# USB.net
KiCad netlist of a schematic drawn in Altium Designer
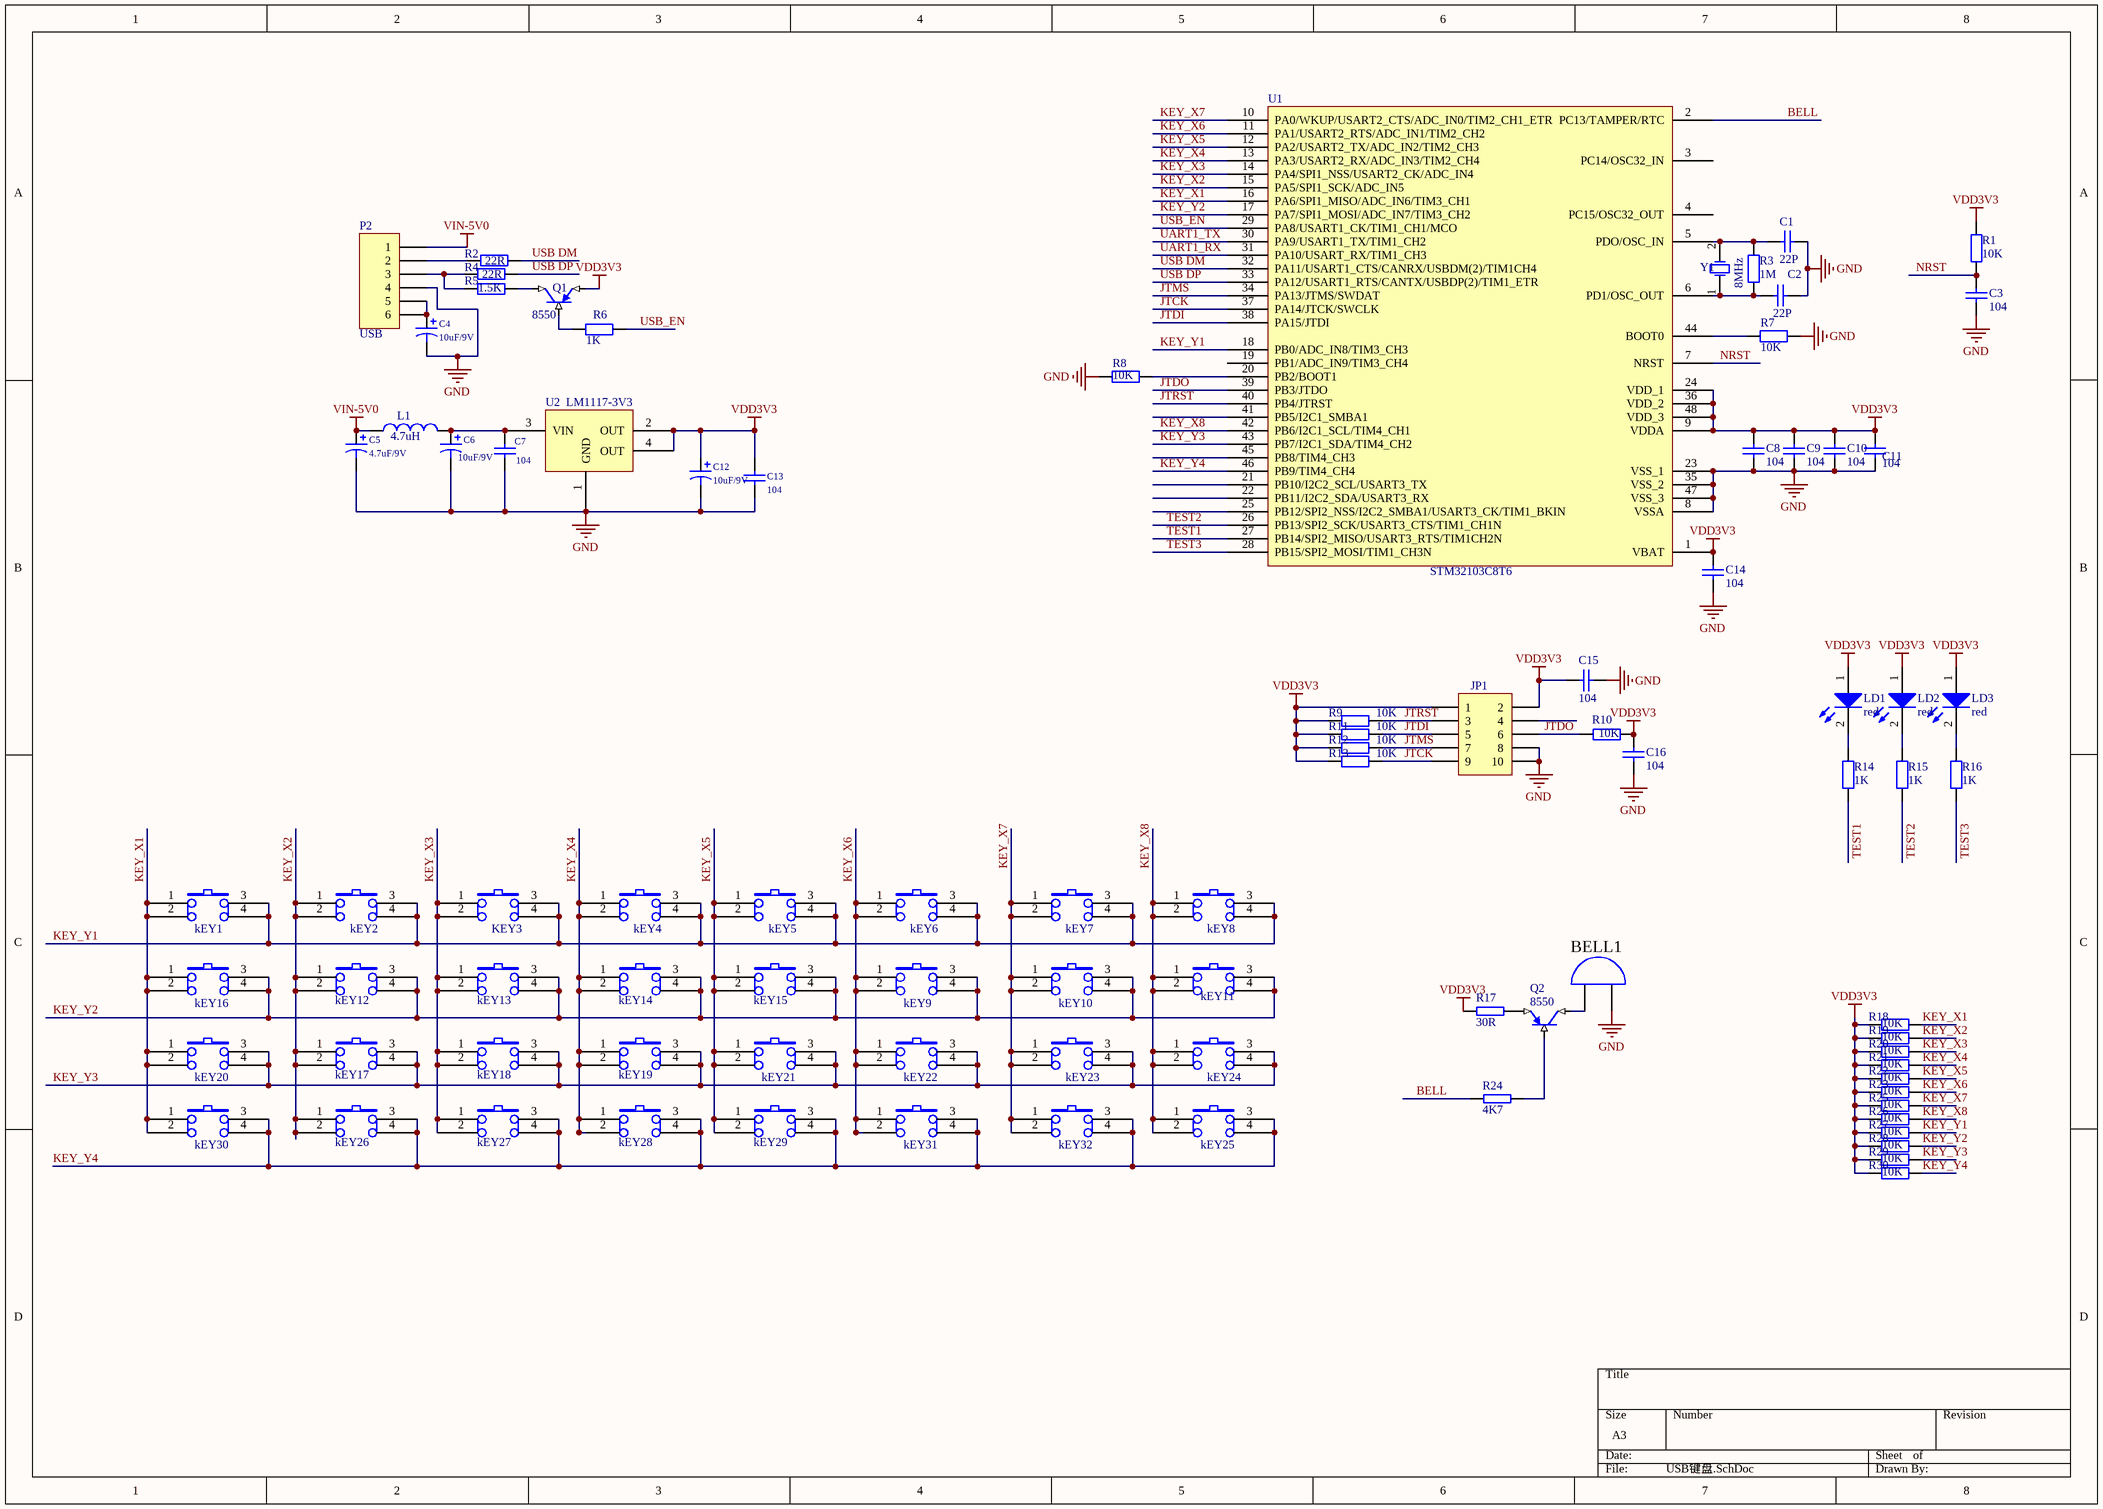
[diagram p0: USB键盘.SchDoc]

(export (version "E")
  (design (tool "Eeschema 10.0.6"))
  (components
    (comp (ref "BELL1")
      (value "JIAO1")
      (footprint "BELL")
      (description "Bell")
      (libsource (lib "*") (part "BELL"))
    )
    (comp (ref "C1")
      (value "22P")
      (footprint "SMD-0805")
      (description "Capacitor")
      (fields (field (name "PUBLISHER") "Altium Limited"))
      (libsource (lib "Miscellaneous Devices") (part "Cap"))
    )
    (comp (ref "C2")
      (value "22P")
      (footprint "SMD-0805")
      (description "Capacitor")
      (fields (field (name "PUBLISHER") "Altium Limited"))
      (libsource (lib "Miscellaneous Devices") (part "Cap"))
    )
    (comp (ref "C3")
      (value "104")
      (footprint "SMD-0805")
      (description "Capacitor")
      (fields (field (name "PUBLISHER") "Altium Limited"))
      (libsource (lib "Miscellaneous Devices") (part "Cap"))
    )
    (comp (ref "C4")
      (value "10uF/9V")
      (footprint "SMD-3528")
      (description "Polarized Capacitor (Radial)")
      (fields (field (name "PUBLISHER") "Altium Limited"))
      (libsource (lib "*") (part "Cap Pol1"))
    )
    (comp (ref "C5")
      (value "4.7uF/9V")
      (footprint "SMD-3528")
      (description "Polarized Capacitor (Radial)")
      (fields (field (name "PUBLISHER") "Altium Limited"))
      (libsource (lib "*") (part "Cap Pol1"))
    )
    (comp (ref "C6")
      (value "10uF/9V")
      (footprint "SMD-3528")
      (description "Polarized Capacitor (Radial)")
      (fields (field (name "PUBLISHER") "Altium Limited"))
      (libsource (lib "*") (part "Cap Pol1"))
    )
    (comp (ref "C7")
      (value "104")
      (footprint "SMD-0805")
      (description "Capacitor")
      (fields (field (name "PUBLISHER") "Altium Limited"))
      (libsource (lib "*") (part "Cap"))
    )
    (comp (ref "C8")
      (value "104")
      (footprint "SMD-0805")
      (description "Capacitor")
      (fields (field (name "PUBLISHER") "Altium Limited"))
      (libsource (lib "Miscellaneous Devices") (part "Cap"))
    )
    (comp (ref "C9")
      (value "104")
      (footprint "SMD-0805")
      (description "Capacitor")
      (fields (field (name "PUBLISHER") "Altium Limited"))
      (libsource (lib "Miscellaneous Devices") (part "Cap"))
    )
    (comp (ref "C10")
      (value "104")
      (footprint "SMD-0805")
      (description "Capacitor")
      (fields (field (name "PUBLISHER") "Altium Limited"))
      (libsource (lib "Miscellaneous Devices") (part "Cap"))
    )
    (comp (ref "C11")
      (value "104")
      (footprint "SMD-0805")
      (description "Capacitor")
      (fields (field (name "PUBLISHER") "Altium Limited"))
      (libsource (lib "Miscellaneous Devices") (part "Cap"))
    )
    (comp (ref "C12")
      (value "10uF/9V")
      (footprint "SMD-3528")
      (description "Polarized Capacitor (Radial)")
      (fields (field (name "PUBLISHER") "Altium Limited"))
      (libsource (lib "*") (part "Cap Pol1"))
    )
    (comp (ref "C13")
      (value "104")
      (footprint "SMD-0805")
      (description "Capacitor")
      (fields (field (name "PUBLISHER") "Altium Limited"))
      (libsource (lib "*") (part "Cap"))
    )
    (comp (ref "C14")
      (value "104")
      (footprint "SMD-0805")
      (description "Capacitor")
      (fields (field (name "PUBLISHER") "Altium Limited"))
      (libsource (lib "Miscellaneous Devices") (part "Cap"))
    )
    (comp (ref "C15")
      (value "104")
      (footprint "SMD-0805")
      (description "Capacitor")
      (fields (field (name "PUBLISHER") "Altium Limited"))
      (libsource (lib "*") (part "Cap"))
    )
    (comp (ref "C16")
      (value "104")
      (footprint "SMD-0805")
      (description "Capacitor")
      (fields (field (name "PUBLISHER") "Altium Limited"))
      (libsource (lib "*") (part "Cap"))
    )
    (comp (ref "JP1")
      (value "~")
      (footprint "JTAG(2.0mm)")
      (description "Header, 5-Pin, Dual row")
      (fields (field (name "PUBLISHER") "Altium Limited"))
      (libsource (lib "*") (part "Header 5X2"))
    )
    (comp (ref "kEY1") (value "~") (footprint "4-16mm-A") (libsource (lib "MY_SCHLIB") (part "sw push")))
    (comp (ref "kEY2") (value "~") (footprint "4-16mm-A") (libsource (lib "MY_SCHLIB") (part "sw push")))
    (comp (ref "KEY3") (value "~") (footprint "4-16mm-A") (libsource (lib "MY_SCHLIB") (part "sw push")))
    (comp (ref "kEY4") (value "~") (footprint "4-16mm-A") (libsource (lib "MY_SCHLIB") (part "sw push")))
    (comp (ref "kEY5") (value "~") (footprint "4-16mm-A") (libsource (lib "MY_SCHLIB") (part "sw push")))
    (comp (ref "kEY6") (value "~") (footprint "4-16mm-A") (libsource (lib "MY_SCHLIB") (part "sw push")))
    (comp (ref "kEY7") (value "~") (footprint "4-16mm-A") (libsource (lib "MY_SCHLIB") (part "sw push")))
    (comp (ref "kEY8") (value "~") (footprint "4-16mm-A") (libsource (lib "MY_SCHLIB") (part "sw push")))
    (comp (ref "kEY9") (value "~") (footprint "4-16mm-A") (libsource (lib "MY_SCHLIB") (part "sw push")))
    (comp (ref "kEY10") (value "~") (footprint "4-16mm-A") (libsource (lib "MY_SCHLIB") (part "sw push")))
    (comp (ref "kEY11") (value "~") (footprint "4-16mm-A") (libsource (lib "MY_SCHLIB") (part "sw push")))
    (comp (ref "kEY12") (value "~") (footprint "4-16mm-A") (libsource (lib "MY_SCHLIB") (part "sw push")))
    (comp (ref "kEY13") (value "~") (footprint "4-16mm-A") (libsource (lib "MY_SCHLIB") (part "sw push")))
    (comp (ref "kEY14") (value "~") (footprint "4-16mm-A") (libsource (lib "MY_SCHLIB") (part "sw push")))
    (comp (ref "kEY15") (value "~") (footprint "4-16mm-A") (libsource (lib "MY_SCHLIB") (part "sw push")))
    (comp (ref "kEY16") (value "~") (footprint "4-16mm-A") (libsource (lib "MY_SCHLIB") (part "sw push")))
    (comp (ref "kEY17") (value "~") (footprint "4-16mm-A") (libsource (lib "MY_SCHLIB") (part "sw push")))
    (comp (ref "kEY18") (value "~") (footprint "4-16mm-A") (libsource (lib "MY_SCHLIB") (part "sw push")))
    (comp (ref "kEY19") (value "~") (footprint "4-16mm-A") (libsource (lib "MY_SCHLIB") (part "sw push")))
    (comp (ref "kEY20") (value "~") (footprint "4-16mm-A") (libsource (lib "MY_SCHLIB") (part "sw push")))
    (comp (ref "kEY21") (value "~") (footprint "4-16mm-A") (libsource (lib "MY_SCHLIB") (part "sw push")))
    (comp (ref "kEY22") (value "~") (footprint "4-16mm-A") (libsource (lib "MY_SCHLIB") (part "sw push")))
    (comp (ref "kEY23") (value "~") (footprint "4-16mm-A") (libsource (lib "MY_SCHLIB") (part "sw push")))
    (comp (ref "kEY24") (value "~") (footprint "4-16mm-A") (libsource (lib "MY_SCHLIB") (part "sw push")))
    (comp (ref "kEY25") (value "~") (footprint "4-16mm-A") (libsource (lib "MY_SCHLIB") (part "sw push")))
    (comp (ref "kEY26") (value "~") (footprint "4-16mm-A") (libsource (lib "MY_SCHLIB") (part "sw push")))
    (comp (ref "kEY27") (value "~") (footprint "4-16mm-A") (libsource (lib "MY_SCHLIB") (part "sw push")))
    (comp (ref "kEY28") (value "~") (footprint "4-16mm-A") (libsource (lib "MY_SCHLIB") (part "sw push")))
    (comp (ref "kEY29") (value "~") (footprint "4-16mm-A") (libsource (lib "MY_SCHLIB") (part "sw push")))
    (comp (ref "kEY30") (value "~") (footprint "4-16mm-A") (libsource (lib "MY_SCHLIB") (part "sw push")))
    (comp (ref "kEY31") (value "~") (footprint "4-16mm-A") (libsource (lib "MY_SCHLIB") (part "sw push")))
    (comp (ref "kEY32") (value "~") (footprint "4-16mm-A") (libsource (lib "MY_SCHLIB") (part "sw push")))
    (comp (ref "L1")
      (value "4.7uH")
      (footprint "SMD-0805")
      (description "Inductor")
      (fields (field (name "PUBLISHER") "Altium Limited"))
      (libsource (lib "*") (part "Inductor"))
    )
    (comp (ref "LD1")
      (value "red")
      (footprint "SMD-LED")
      (description "Typical RED, GREEN, YELLOW, AMBER GaAs LED")
      (fields (field (name "PUBLISHER") "*"))
      (libsource (lib "*") (part "LED2"))
    )
    (comp (ref "LD2")
      (value "red")
      (footprint "SMD-LED")
      (description "Typical RED, GREEN, YELLOW, AMBER GaAs LED")
      (fields (field (name "PUBLISHER") "*"))
      (libsource (lib "*") (part "LED2"))
    )
    (comp (ref "LD3")
      (value "red")
      (footprint "SMD-LED")
      (description "Typical RED, GREEN, YELLOW, AMBER GaAs LED")
      (fields (field (name "PUBLISHER") "*"))
      (libsource (lib "*") (part "LED2"))
    )
    (comp (ref "P2")
      (value "USB")
      (footprint "USB-A")
      (description "Header, 6-Pin")
      (fields (field (name "PUBLISHER") "Altium Limited"))
      (libsource (lib "Miscellaneous Connectors") (part "Header 6"))
    )
    (comp (ref "Q1")
      (value "8550")
      (footprint "SOT-23")
      (description "PNP BJT")
      (libsource (lib "*") (part "8550"))
    )
    (comp (ref "Q2")
      (value "8550")
      (footprint "SOT-23")
      (description "PNP BJT")
      (libsource (lib "*") (part "8550"))
    )
    (comp (ref "R1")
      (value "10K")
      (footprint "SMD-0805")
      (description "Resistor")
      (fields (field (name "PUBLISHER") "Altium Limited"))
      (libsource (lib "") (part "Res2_3"))
    )
    (comp (ref "R2")
      (value "22R")
      (footprint "SMD-0805")
      (description "Resistor")
      (fields (field (name "PUBLISHER") "Altium Limited"))
      (libsource (lib "Miscellaneous Devices") (part "Res2"))
    )
    (comp (ref "R3")
      (value "1M")
      (footprint "SMD-0805")
      (description "Resistor")
      (fields (field (name "PUBLISHER") "Altium Limited"))
      (libsource (lib "") (part "Res2_3"))
    )
    (comp (ref "R4")
      (value "22R")
      (footprint "SMD-0805")
      (description "Resistor")
      (fields (field (name "PUBLISHER") "Altium Limited"))
      (libsource (lib "Miscellaneous Devices") (part "Res2"))
    )
    (comp (ref "R5")
      (value "1.5K")
      (footprint "SMD-0805")
      (description "Resistor")
      (fields (field (name "PUBLISHER") "Altium Limited"))
      (libsource (lib "Miscellaneous Devices") (part "Res2"))
    )
    (comp (ref "R6")
      (value "1K")
      (footprint "SMD-0805")
      (description "Resistor")
      (fields (field (name "PUBLISHER") "Altium Limited"))
      (libsource (lib "Miscellaneous Devices") (part "Res2"))
    )
    (comp (ref "R7")
      (value "10K")
      (footprint "SMD-0805")
      (description "Resistor")
      (fields (field (name "PUBLISHER") "Altium Limited"))
      (libsource (lib "") (part "Res2_1"))
    )
    (comp (ref "R8")
      (value "10K")
      (footprint "SMD-0805")
      (description "Resistor")
      (fields (field (name "PUBLISHER") "Altium Limited"))
      (libsource (lib "") (part "Res2_1"))
    )
    (comp (ref "R9")
      (value "10K")
      (footprint "SMD-0805")
      (description "Resistor")
      (fields (field (name "PUBLISHER") "Altium Limited"))
      (libsource (lib "") (part "Res2_1"))
    )
    (comp (ref "R10")
      (value "10K")
      (footprint "SMD-0805")
      (description "Resistor")
      (fields (field (name "PUBLISHER") "Altium Limited"))
      (libsource (lib "") (part "Res2_1"))
    )
    (comp (ref "R11")
      (value "10K")
      (footprint "SMD-0805")
      (description "Resistor")
      (fields (field (name "PUBLISHER") "Altium Limited"))
      (libsource (lib "") (part "Res2_1"))
    )
    (comp (ref "R12")
      (value "10K")
      (footprint "SMD-0805")
      (description "Resistor")
      (fields (field (name "PUBLISHER") "Altium Limited"))
      (libsource (lib "") (part "Res2_1"))
    )
    (comp (ref "R13")
      (value "10K")
      (footprint "SMD-0805")
      (description "Resistor")
      (fields (field (name "PUBLISHER") "Altium Limited"))
      (libsource (lib "") (part "Res2_1"))
    )
    (comp (ref "R14")
      (value "1K")
      (footprint "SMD-0805")
      (description "Resistor")
      (fields (field (name "PUBLISHER") "Altium Limited"))
      (libsource (lib "") (part "Res2_2"))
    )
    (comp (ref "R15")
      (value "1K")
      (footprint "SMD-0805")
      (description "Resistor")
      (fields (field (name "PUBLISHER") "Altium Limited"))
      (libsource (lib "") (part "Res2_2"))
    )
    (comp (ref "R16")
      (value "1K")
      (footprint "SMD-0805")
      (description "Resistor")
      (fields (field (name "PUBLISHER") "Altium Limited"))
      (libsource (lib "") (part "Res2_2"))
    )
    (comp (ref "R17") (value "30R") (footprint "SMD-0805") (libsource (lib "*") (part "RES")))
    (comp (ref "R18")
      (value "10K")
      (footprint "SMD-0805")
      (description "Resistor")
      (fields (field (name "PUBLISHER") "Altium Limited"))
      (libsource (lib "Miscellaneous Devices") (part "Res2"))
    )
    (comp (ref "R19")
      (value "10K")
      (footprint "SMD-0805")
      (description "Resistor")
      (fields (field (name "PUBLISHER") "Altium Limited"))
      (libsource (lib "Miscellaneous Devices") (part "Res2"))
    )
    (comp (ref "R20")
      (value "10K")
      (footprint "SMD-0805")
      (description "Resistor")
      (fields (field (name "PUBLISHER") "Altium Limited"))
      (libsource (lib "Miscellaneous Devices") (part "Res2"))
    )
    (comp (ref "R21")
      (value "10K")
      (footprint "SMD-0805")
      (description "Resistor")
      (fields (field (name "PUBLISHER") "Altium Limited"))
      (libsource (lib "Miscellaneous Devices") (part "Res2"))
    )
    (comp (ref "R22")
      (value "10K")
      (footprint "SMD-0805")
      (description "Resistor")
      (fields (field (name "PUBLISHER") "Altium Limited"))
      (libsource (lib "Miscellaneous Devices") (part "Res2"))
    )
    (comp (ref "R23")
      (value "10K")
      (footprint "SMD-0805")
      (description "Resistor")
      (fields (field (name "PUBLISHER") "Altium Limited"))
      (libsource (lib "Miscellaneous Devices") (part "Res2"))
    )
    (comp (ref "R24") (value "4K7") (footprint "SMD-0805") (libsource (lib "*") (part "RES")))
    (comp (ref "R25")
      (value "10K")
      (footprint "SMD-0805")
      (description "Resistor")
      (fields (field (name "PUBLISHER") "Altium Limited"))
      (libsource (lib "Miscellaneous Devices") (part "Res2"))
    )
    (comp (ref "R26")
      (value "10K")
      (footprint "SMD-0805")
      (description "Resistor")
      (fields (field (name "PUBLISHER") "Altium Limited"))
      (libsource (lib "Miscellaneous Devices") (part "Res2"))
    )
    (comp (ref "R27")
      (value "10K")
      (footprint "SMD-0805")
      (description "Resistor")
      (fields (field (name "PUBLISHER") "Altium Limited"))
      (libsource (lib "Miscellaneous Devices") (part "Res2"))
    )
    (comp (ref "R28")
      (value "10K")
      (footprint "SMD-0805")
      (description "Resistor")
      (fields (field (name "PUBLISHER") "Altium Limited"))
      (libsource (lib "Miscellaneous Devices") (part "Res2"))
    )
    (comp (ref "R29")
      (value "10K")
      (footprint "SMD-0805")
      (description "Resistor")
      (fields (field (name "PUBLISHER") "Altium Limited"))
      (libsource (lib "Miscellaneous Devices") (part "Res2"))
    )
    (comp (ref "R30")
      (value "10K")
      (footprint "SMD-0805")
      (description "Resistor")
      (fields (field (name "PUBLISHER") "Altium Limited"))
      (libsource (lib "Miscellaneous Devices") (part "Res2"))
    )
    (comp (ref "U1")
      (value "STM32103C8T6")
      (footprint "LQFP-48")
      (libsource (lib "MY_SCHLIB") (part "STM32103C8T6"))
    )
    (comp (ref "U2") (value "LM1117-3V3") (footprint "SOT-233") (libsource (lib "MY_SCHLIB") (part "LM1117")))
    (comp (ref "Y1")
      (value "8MHz")
      (footprint "XTLA")
      (description "晶体振荡器")
      (fields (field (name "PUBLISHER") "Altium Limited"))
      (libsource (lib "SWS库制作") (part "XTAL"))
    )
  )
  (nets
    (net (code "1") (name "/BELL") (class "Default")
      (node (ref "R24") (pin "2") (pinfunction "10_2") (pintype "passive"))
      (node (ref "U1") (pin "2") (pinfunction "PC13/TAMPER/RTC_2") (pintype "passive"))
    )
    (net (code "2") (name "/JTCK") (class "Default")
      (node (ref "JP1") (pin "9") (pinfunction "9_9") (pintype "passive"))
      (node (ref "R13") (pin "1") (pinfunction "1_1") (pintype "passive"))
      (node (ref "U1") (pin "37") (pinfunction "PA14/JTCK/SWCLK_37") (pintype "passive"))
    )
    (net (code "3") (name "/JTDI") (class "Default")
      (node (ref "JP1") (pin "5") (pinfunction "5_5") (pintype "passive"))
      (node (ref "R11") (pin "1") (pinfunction "1_1") (pintype "passive"))
      (node (ref "U1") (pin "38") (pinfunction "PA15/JTDI_38") (pintype "passive"))
    )
    (net (code "4") (name "/JTDO") (class "Default")
      (node (ref "JP1") (pin "6") (pinfunction "6_6") (pintype "passive"))
      (node (ref "R10") (pin "2") (pinfunction "2_2") (pintype "passive"))
      (node (ref "U1") (pin "39") (pinfunction "PB3/JTDO_39") (pintype "passive"))
    )
    (net (code "5") (name "/JTMS") (class "Default")
      (node (ref "JP1") (pin "7") (pinfunction "7_7") (pintype "passive"))
      (node (ref "R12") (pin "1") (pinfunction "1_1") (pintype "passive"))
      (node (ref "U1") (pin "34") (pinfunction "PA13/JTMS/SWDAT_34") (pintype "passive"))
    )
    (net (code "6") (name "/JTRST") (class "Default")
      (node (ref "JP1") (pin "3") (pinfunction "3_3") (pintype "passive"))
      (node (ref "R9") (pin "1") (pinfunction "1_1") (pintype "passive"))
      (node (ref "U1") (pin "40") (pinfunction "PB4/JTRST_40") (pintype "passive"))
    )
    (net (code "7") (name "/KEY_X1") (class "Default")
      (node (ref "R18") (pin "2") (pinfunction "2_2") (pintype "passive"))
      (node (ref "U1") (pin "16") (pinfunction "PA6/SPI1_MISO/ADC_IN6/TIM3_CH1_16") (pintype "passive"))
      (node (ref "kEY1") (pin "1") (pinfunction "1_1") (pintype "passive"))
      (node (ref "kEY1") (pin "2") (pinfunction "2_2") (pintype "passive"))
      (node (ref "kEY16") (pin "1") (pinfunction "1_1") (pintype "passive"))
      (node (ref "kEY16") (pin "2") (pinfunction "2_2") (pintype "passive"))
      (node (ref "kEY20") (pin "1") (pinfunction "1_1") (pintype "passive"))
      (node (ref "kEY20") (pin "2") (pinfunction "2_2") (pintype "passive"))
      (node (ref "kEY30") (pin "1") (pinfunction "1_1") (pintype "passive"))
      (node (ref "kEY30") (pin "2") (pinfunction "2_2") (pintype "passive"))
    )
    (net (code "8") (name "/KEY_X2") (class "Default")
      (node (ref "R19") (pin "2") (pinfunction "2_2") (pintype "passive"))
      (node (ref "U1") (pin "15") (pinfunction "PA5/SPI1_SCK/ADC_IN5_15") (pintype "passive"))
      (node (ref "kEY12") (pin "1") (pinfunction "1_1") (pintype "passive"))
      (node (ref "kEY12") (pin "2") (pinfunction "2_2") (pintype "passive"))
      (node (ref "kEY17") (pin "1") (pinfunction "1_1") (pintype "passive"))
      (node (ref "kEY17") (pin "2") (pinfunction "2_2") (pintype "passive"))
      (node (ref "kEY2") (pin "1") (pinfunction "1_1") (pintype "passive"))
      (node (ref "kEY2") (pin "2") (pinfunction "2_2") (pintype "passive"))
      (node (ref "kEY26") (pin "1") (pinfunction "1_1") (pintype "passive"))
      (node (ref "kEY26") (pin "2") (pinfunction "2_2") (pintype "passive"))
    )
    (net (code "9") (name "/KEY_X3") (class "Default")
      (node (ref "KEY3") (pin "1") (pinfunction "1_1") (pintype "passive"))
      (node (ref "KEY3") (pin "2") (pinfunction "2_2") (pintype "passive"))
      (node (ref "R20") (pin "2") (pinfunction "2_2") (pintype "passive"))
      (node (ref "U1") (pin "14") (pinfunction "PA4/SPI1_NSS/USART2_CK/ADC_IN4_14") (pintype "passive"))
      (node (ref "kEY13") (pin "1") (pinfunction "1_1") (pintype "passive"))
      (node (ref "kEY13") (pin "2") (pinfunction "2_2") (pintype "passive"))
      (node (ref "kEY18") (pin "1") (pinfunction "1_1") (pintype "passive"))
      (node (ref "kEY18") (pin "2") (pinfunction "2_2") (pintype "passive"))
      (node (ref "kEY27") (pin "1") (pinfunction "1_1") (pintype "passive"))
      (node (ref "kEY27") (pin "2") (pinfunction "2_2") (pintype "passive"))
    )
    (net (code "10") (name "/KEY_X4") (class "Default")
      (node (ref "R21") (pin "2") (pinfunction "2_2") (pintype "passive"))
      (node (ref "U1") (pin "13") (pinfunction "PA3/USART2_RX/ADC_IN3/TIM2_CH4_13") (pintype "passive"))
      (node (ref "kEY14") (pin "1") (pinfunction "1_1") (pintype "passive"))
      (node (ref "kEY14") (pin "2") (pinfunction "2_2") (pintype "passive"))
      (node (ref "kEY19") (pin "1") (pinfunction "1_1") (pintype "passive"))
      (node (ref "kEY19") (pin "2") (pinfunction "2_2") (pintype "passive"))
      (node (ref "kEY28") (pin "1") (pinfunction "1_1") (pintype "passive"))
      (node (ref "kEY28") (pin "2") (pinfunction "2_2") (pintype "passive"))
      (node (ref "kEY4") (pin "1") (pinfunction "1_1") (pintype "passive"))
      (node (ref "kEY4") (pin "2") (pinfunction "2_2") (pintype "passive"))
    )
    (net (code "11") (name "/KEY_X5") (class "Default")
      (node (ref "R22") (pin "2") (pinfunction "2_2") (pintype "passive"))
      (node (ref "U1") (pin "12") (pinfunction "PA2/USART2_TX/ADC_IN2/TIM2_CH3_12") (pintype "passive"))
      (node (ref "kEY15") (pin "1") (pinfunction "1_1") (pintype "passive"))
      (node (ref "kEY15") (pin "2") (pinfunction "2_2") (pintype "passive"))
      (node (ref "kEY21") (pin "1") (pinfunction "1_1") (pintype "passive"))
      (node (ref "kEY21") (pin "2") (pinfunction "2_2") (pintype "passive"))
      (node (ref "kEY29") (pin "1") (pinfunction "1_1") (pintype "passive"))
      (node (ref "kEY29") (pin "2") (pinfunction "2_2") (pintype "passive"))
      (node (ref "kEY5") (pin "1") (pinfunction "1_1") (pintype "passive"))
      (node (ref "kEY5") (pin "2") (pinfunction "2_2") (pintype "passive"))
    )
    (net (code "12") (name "/KEY_X6") (class "Default")
      (node (ref "R23") (pin "2") (pinfunction "2_2") (pintype "passive"))
      (node (ref "U1") (pin "11") (pinfunction "PA1/USART2_RTS/ADC_IN1/TIM2_CH2_11") (pintype "passive"))
      (node (ref "kEY22") (pin "1") (pinfunction "1_1") (pintype "passive"))
      (node (ref "kEY22") (pin "2") (pinfunction "2_2") (pintype "passive"))
      (node (ref "kEY31") (pin "1") (pinfunction "1_1") (pintype "passive"))
      (node (ref "kEY31") (pin "2") (pinfunction "2_2") (pintype "passive"))
      (node (ref "kEY6") (pin "1") (pinfunction "1_1") (pintype "passive"))
      (node (ref "kEY6") (pin "2") (pinfunction "2_2") (pintype "passive"))
      (node (ref "kEY9") (pin "1") (pinfunction "1_1") (pintype "passive"))
      (node (ref "kEY9") (pin "2") (pinfunction "2_2") (pintype "passive"))
    )
    (net (code "13") (name "/KEY_X7") (class "Default")
      (node (ref "R25") (pin "2") (pinfunction "2_2") (pintype "passive"))
      (node (ref "U1") (pin "10") (pinfunction "PA0/WKUP/USART2_CTS/ADC_IN0/TIM2_CH1_ETR_10") (pintype "passive"))
      (node (ref "kEY10") (pin "1") (pinfunction "1_1") (pintype "passive"))
      (node (ref "kEY10") (pin "2") (pinfunction "2_2") (pintype "passive"))
      (node (ref "kEY23") (pin "1") (pinfunction "1_1") (pintype "passive"))
      (node (ref "kEY23") (pin "2") (pinfunction "2_2") (pintype "passive"))
      (node (ref "kEY32") (pin "1") (pinfunction "1_1") (pintype "passive"))
      (node (ref "kEY32") (pin "2") (pinfunction "2_2") (pintype "passive"))
      (node (ref "kEY7") (pin "1") (pinfunction "1_1") (pintype "passive"))
      (node (ref "kEY7") (pin "2") (pinfunction "2_2") (pintype "passive"))
    )
    (net (code "14") (name "/KEY_X8") (class "Default")
      (node (ref "R26") (pin "2") (pinfunction "2_2") (pintype "passive"))
      (node (ref "U1") (pin "42") (pinfunction "PB6/I2C1_SCL/TIM4_CH1_42") (pintype "passive"))
      (node (ref "kEY11") (pin "1") (pinfunction "1_1") (pintype "passive"))
      (node (ref "kEY11") (pin "2") (pinfunction "2_2") (pintype "passive"))
      (node (ref "kEY24") (pin "1") (pinfunction "1_1") (pintype "passive"))
      (node (ref "kEY24") (pin "2") (pinfunction "2_2") (pintype "passive"))
      (node (ref "kEY25") (pin "1") (pinfunction "1_1") (pintype "passive"))
      (node (ref "kEY25") (pin "2") (pinfunction "2_2") (pintype "passive"))
      (node (ref "kEY8") (pin "1") (pinfunction "1_1") (pintype "passive"))
      (node (ref "kEY8") (pin "2") (pinfunction "2_2") (pintype "passive"))
    )
    (net (code "15") (name "/KEY_Y1") (class "Default")
      (node (ref "KEY3") (pin "3") (pinfunction "2_3") (pintype "passive"))
      (node (ref "KEY3") (pin "4") (pinfunction "6_4") (pintype "passive"))
      (node (ref "R27") (pin "2") (pinfunction "2_2") (pintype "passive"))
      (node (ref "U1") (pin "18") (pinfunction "PB0/ADC_IN8/TIM3_CH3_18") (pintype "passive"))
      (node (ref "kEY1") (pin "3") (pinfunction "2_3") (pintype "passive"))
      (node (ref "kEY1") (pin "4") (pinfunction "6_4") (pintype "passive"))
      (node (ref "kEY2") (pin "3") (pinfunction "2_3") (pintype "passive"))
      (node (ref "kEY2") (pin "4") (pinfunction "6_4") (pintype "passive"))
      (node (ref "kEY4") (pin "3") (pinfunction "2_3") (pintype "passive"))
      (node (ref "kEY4") (pin "4") (pinfunction "6_4") (pintype "passive"))
      (node (ref "kEY5") (pin "3") (pinfunction "2_3") (pintype "passive"))
      (node (ref "kEY5") (pin "4") (pinfunction "6_4") (pintype "passive"))
      (node (ref "kEY6") (pin "3") (pinfunction "2_3") (pintype "passive"))
      (node (ref "kEY6") (pin "4") (pinfunction "6_4") (pintype "passive"))
      (node (ref "kEY7") (pin "3") (pinfunction "2_3") (pintype "passive"))
      (node (ref "kEY7") (pin "4") (pinfunction "6_4") (pintype "passive"))
      (node (ref "kEY8") (pin "3") (pinfunction "2_3") (pintype "passive"))
      (node (ref "kEY8") (pin "4") (pinfunction "6_4") (pintype "passive"))
    )
    (net (code "16") (name "/KEY_Y2") (class "Default")
      (node (ref "R28") (pin "2") (pinfunction "2_2") (pintype "passive"))
      (node (ref "U1") (pin "17") (pinfunction "PA7/SPI1_MOSI/ADC_IN7/TIM3_CH2_17") (pintype "passive"))
      (node (ref "kEY10") (pin "3") (pinfunction "2_3") (pintype "passive"))
      (node (ref "kEY10") (pin "4") (pinfunction "6_4") (pintype "passive"))
      (node (ref "kEY11") (pin "3") (pinfunction "2_3") (pintype "passive"))
      (node (ref "kEY11") (pin "4") (pinfunction "6_4") (pintype "passive"))
      (node (ref "kEY12") (pin "3") (pinfunction "2_3") (pintype "passive"))
      (node (ref "kEY12") (pin "4") (pinfunction "6_4") (pintype "passive"))
      (node (ref "kEY13") (pin "3") (pinfunction "2_3") (pintype "passive"))
      (node (ref "kEY13") (pin "4") (pinfunction "6_4") (pintype "passive"))
      (node (ref "kEY14") (pin "3") (pinfunction "2_3") (pintype "passive"))
      (node (ref "kEY14") (pin "4") (pinfunction "6_4") (pintype "passive"))
      (node (ref "kEY15") (pin "3") (pinfunction "2_3") (pintype "passive"))
      (node (ref "kEY15") (pin "4") (pinfunction "6_4") (pintype "passive"))
      (node (ref "kEY16") (pin "3") (pinfunction "2_3") (pintype "passive"))
      (node (ref "kEY16") (pin "4") (pinfunction "6_4") (pintype "passive"))
      (node (ref "kEY9") (pin "3") (pinfunction "2_3") (pintype "passive"))
      (node (ref "kEY9") (pin "4") (pinfunction "6_4") (pintype "passive"))
    )
    (net (code "17") (name "/KEY_Y3") (class "Default")
      (node (ref "R29") (pin "2") (pinfunction "2_2") (pintype "passive"))
      (node (ref "U1") (pin "43") (pinfunction "PB7/I2C1_SDA/TIM4_CH2_43") (pintype "passive"))
      (node (ref "kEY17") (pin "3") (pinfunction "2_3") (pintype "passive"))
      (node (ref "kEY17") (pin "4") (pinfunction "6_4") (pintype "passive"))
      (node (ref "kEY18") (pin "3") (pinfunction "2_3") (pintype "passive"))
      (node (ref "kEY18") (pin "4") (pinfunction "6_4") (pintype "passive"))
      (node (ref "kEY19") (pin "3") (pinfunction "2_3") (pintype "passive"))
      (node (ref "kEY19") (pin "4") (pinfunction "6_4") (pintype "passive"))
      (node (ref "kEY20") (pin "3") (pinfunction "2_3") (pintype "passive"))
      (node (ref "kEY20") (pin "4") (pinfunction "6_4") (pintype "passive"))
      (node (ref "kEY21") (pin "3") (pinfunction "2_3") (pintype "passive"))
      (node (ref "kEY21") (pin "4") (pinfunction "6_4") (pintype "passive"))
      (node (ref "kEY22") (pin "3") (pinfunction "2_3") (pintype "passive"))
      (node (ref "kEY22") (pin "4") (pinfunction "6_4") (pintype "passive"))
      (node (ref "kEY23") (pin "3") (pinfunction "2_3") (pintype "passive"))
      (node (ref "kEY23") (pin "4") (pinfunction "6_4") (pintype "passive"))
      (node (ref "kEY24") (pin "3") (pinfunction "2_3") (pintype "passive"))
      (node (ref "kEY24") (pin "4") (pinfunction "6_4") (pintype "passive"))
    )
    (net (code "18") (name "/KEY_Y4") (class "Default")
      (node (ref "R30") (pin "2") (pinfunction "2_2") (pintype "passive"))
      (node (ref "U1") (pin "46") (pinfunction "PB9/TIM4_CH4_46") (pintype "passive"))
      (node (ref "kEY25") (pin "3") (pinfunction "2_3") (pintype "passive"))
      (node (ref "kEY25") (pin "4") (pinfunction "6_4") (pintype "passive"))
      (node (ref "kEY26") (pin "3") (pinfunction "2_3") (pintype "passive"))
      (node (ref "kEY26") (pin "4") (pinfunction "6_4") (pintype "passive"))
      (node (ref "kEY27") (pin "3") (pinfunction "2_3") (pintype "passive"))
      (node (ref "kEY27") (pin "4") (pinfunction "6_4") (pintype "passive"))
      (node (ref "kEY28") (pin "3") (pinfunction "2_3") (pintype "passive"))
      (node (ref "kEY28") (pin "4") (pinfunction "6_4") (pintype "passive"))
      (node (ref "kEY29") (pin "3") (pinfunction "2_3") (pintype "passive"))
      (node (ref "kEY29") (pin "4") (pinfunction "6_4") (pintype "passive"))
      (node (ref "kEY30") (pin "3") (pinfunction "2_3") (pintype "passive"))
      (node (ref "kEY30") (pin "4") (pinfunction "6_4") (pintype "passive"))
      (node (ref "kEY31") (pin "3") (pinfunction "2_3") (pintype "passive"))
      (node (ref "kEY31") (pin "4") (pinfunction "6_4") (pintype "passive"))
      (node (ref "kEY32") (pin "3") (pinfunction "2_3") (pintype "passive"))
      (node (ref "kEY32") (pin "4") (pinfunction "6_4") (pintype "passive"))
    )
    (net (code "19") (name "/NRST") (class "Default")
      (node (ref "C3") (pin "2") (pinfunction "2_2") (pintype "passive"))
      (node (ref "R1") (pin "1") (pinfunction "1_1") (pintype "passive"))
      (node (ref "U1") (pin "7") (pinfunction "NRST_7") (pintype "passive"))
    )
    (net (code "20") (name "/TEST1") (class "Default")
      (node (ref "R14") (pin "2") (pinfunction "2_2") (pintype "passive"))
      (node (ref "U1") (pin "27") (pinfunction "PB14/SPI2_MISO/USART3_RTS/TIM1CH2N_27") (pintype "passive"))
    )
    (net (code "21") (name "/TEST2") (class "Default")
      (node (ref "R15") (pin "2") (pinfunction "2_2") (pintype "passive"))
      (node (ref "U1") (pin "26") (pinfunction "PB13/SPI2_SCK/USART3_CTS/TIM1_CH1N_26") (pintype "passive"))
    )
    (net (code "22") (name "/TEST3") (class "Default")
      (node (ref "R16") (pin "2") (pinfunction "2_2") (pintype "passive"))
      (node (ref "U1") (pin "28") (pinfunction "PB15/SPI2_MOSI/TIM1_CH3N_28") (pintype "passive"))
    )
    (net (code "23") (name "/UART1_RX") (class "Default")
      (node (ref "U1") (pin "31") (pinfunction "PA10/USART_RX/TIM1_CH3_31") (pintype "passive"))
    )
    (net (code "24") (name "/UART1_TX") (class "Default")
      (node (ref "U1") (pin "30") (pinfunction "PA9/USART1_TX/TIM1_CH2_30") (pintype "passive"))
    )
    (net (code "25") (name "/USB DM") (class "Default")
      (node (ref "R2") (pin "2") (pinfunction "2_2") (pintype "passive"))
      (node (ref "U1") (pin "32") (pinfunction "PA11/USART1_CTS/CANRX/USBDM(2)/TIM1CH4_32") (pintype "passive"))
    )
    (net (code "26") (name "/USB DP") (class "Default")
      (node (ref "R4") (pin "2") (pinfunction "2_2") (pintype "passive"))
      (node (ref "U1") (pin "33") (pinfunction "PA12/USART1_RTS/CANTX/USBDP(2)/TIM1_ETR_33") (pintype "passive"))
    )
    (net (code "27") (name "/USB_EN") (class "Default")
      (node (ref "R6") (pin "2") (pinfunction "2_2") (pintype "passive"))
      (node (ref "U1") (pin "29") (pinfunction "PA8/USART1_CK/TIM1_CH1/MCO_29") (pintype "passive"))
    )
    (net (code "28") (name "GND") (class "Default")
      (node (ref "BELL1") (pin "2") (pinfunction "B_2") (pintype "passive"))
      (node (ref "C1") (pin "2") (pinfunction "2_2") (pintype "passive"))
      (node (ref "C10") (pin "1") (pinfunction "1_1") (pintype "passive"))
      (node (ref "C11") (pin "1") (pinfunction "1_1") (pintype "passive"))
      (node (ref "C12") (pin "2") (pinfunction "2_2") (pintype "passive"))
      (node (ref "C13") (pin "2") (pinfunction "2_2") (pintype "passive"))
      (node (ref "C14") (pin "1") (pinfunction "1_1") (pintype "passive"))
      (node (ref "C15") (pin "1") (pinfunction "1_1") (pintype "passive"))
      (node (ref "C16") (pin "1") (pinfunction "1_1") (pintype "passive"))
      (node (ref "C2") (pin "2") (pinfunction "2_2") (pintype "passive"))
      (node (ref "C3") (pin "1") (pinfunction "1_1") (pintype "passive"))
      (node (ref "C4") (pin "2") (pinfunction "2_2") (pintype "passive"))
      (node (ref "C5") (pin "2") (pinfunction "2_2") (pintype "passive"))
      (node (ref "C6") (pin "2") (pinfunction "2_2") (pintype "passive"))
      (node (ref "C7") (pin "1") (pinfunction "1_1") (pintype "passive"))
      (node (ref "C8") (pin "1") (pinfunction "1_1") (pintype "passive"))
      (node (ref "C9") (pin "1") (pinfunction "1_1") (pintype "passive"))
      (node (ref "JP1") (pin "10") (pinfunction "10_10") (pintype "passive"))
      (node (ref "JP1") (pin "8") (pinfunction "8_8") (pintype "passive"))
      (node (ref "P2") (pin "4") (pinfunction "4_4") (pintype "passive"))
      (node (ref "R7") (pin "1") (pinfunction "1_1") (pintype "passive"))
      (node (ref "R8") (pin "2") (pinfunction "2_2") (pintype "passive"))
      (node (ref "U1") (pin "23") (pinfunction "VSS_1_23") (pintype "passive"))
      (node (ref "U1") (pin "35") (pinfunction "VSS_2_35") (pintype "passive"))
      (node (ref "U1") (pin "47") (pinfunction "VSS_3_47") (pintype "passive"))
      (node (ref "U1") (pin "8") (pinfunction "VSSA_8") (pintype "passive"))
      (node (ref "U2") (pin "1") (pinfunction "GND_1") (pintype "passive"))
    )
    (net (code "29") (name "Net-(BELL1-A)") (class "Default")
      (node (ref "BELL1") (pin "1") (pinfunction "A_1") (pintype "passive"))
      (node (ref "Q2") (pin "3") (pinfunction "C_3") (pintype "input"))
    )
    (net (code "30") (name "Net-(C4-Pad1)") (class "Default")
      (node (ref "C4") (pin "1") (pinfunction "1_1") (pintype "passive"))
      (node (ref "P2") (pin "5") (pinfunction "5_5") (pintype "passive"))
      (node (ref "P2") (pin "6") (pinfunction "6_6") (pintype "passive"))
    )
    (net (code "31") (name "Net-(LD1-K)") (class "Default")
      (node (ref "LD1") (pin "2") (pinfunction "K_2") (pintype "passive"))
      (node (ref "R14") (pin "1") (pinfunction "1_1") (pintype "passive"))
    )
    (net (code "32") (name "Net-(LD2-K)") (class "Default")
      (node (ref "LD2") (pin "2") (pinfunction "K_2") (pintype "passive"))
      (node (ref "R15") (pin "1") (pinfunction "1_1") (pintype "passive"))
    )
    (net (code "33") (name "Net-(LD3-K)") (class "Default")
      (node (ref "LD3") (pin "2") (pinfunction "K_2") (pintype "passive"))
      (node (ref "R16") (pin "1") (pinfunction "1_1") (pintype "passive"))
    )
    (net (code "34") (name "Net-(P2-Pad2)") (class "Default")
      (node (ref "P2") (pin "2") (pinfunction "2_2") (pintype "passive"))
      (node (ref "R2") (pin "1") (pinfunction "1_1") (pintype "passive"))
    )
    (net (code "35") (name "Net-(P2-Pad3)") (class "Default")
      (node (ref "P2") (pin "3") (pinfunction "3_3") (pintype "passive"))
      (node (ref "R4") (pin "1") (pinfunction "1_1") (pintype "passive"))
      (node (ref "R5") (pin "1") (pinfunction "1_1") (pintype "passive"))
    )
    (net (code "36") (name "Net-(Q1-B)") (class "Default")
      (node (ref "Q1") (pin "1") (pinfunction "B_1") (pintype "input"))
      (node (ref "R6") (pin "1") (pinfunction "1_1") (pintype "passive"))
    )
    (net (code "37") (name "Net-(Q1-C)") (class "Default")
      (node (ref "Q1") (pin "3") (pinfunction "C_3") (pintype "input"))
      (node (ref "R5") (pin "2") (pinfunction "2_2") (pintype "passive"))
    )
    (net (code "38") (name "Net-(Q2-B)") (class "Default")
      (node (ref "Q2") (pin "1") (pinfunction "B_1") (pintype "input"))
      (node (ref "R24") (pin "1") (pinfunction "1_1") (pintype "passive"))
    )
    (net (code "39") (name "Net-(Q2-E)") (class "Default")
      (node (ref "Q2") (pin "2") (pinfunction "E_2") (pintype "input"))
      (node (ref "R17") (pin "1") (pinfunction "1_1") (pintype "passive"))
    )
    (net (code "40") (name "Net-(U1-BOOT0)") (class "Default")
      (node (ref "R7") (pin "2") (pinfunction "2_2") (pintype "passive"))
      (node (ref "U1") (pin "44") (pinfunction "BOOT0_44") (pintype "passive"))
    )
    (net (code "41") (name "Net-(U1-PB2{slash}BOOT1)") (class "Default")
      (node (ref "R8") (pin "1") (pinfunction "1_1") (pintype "passive"))
      (node (ref "U1") (pin "20") (pinfunction "PB2/BOOT1_20") (pintype "passive"))
    )
    (net (code "42") (name "Net-(U1-PD1{slash}OSC_OUT)") (class "Default")
      (node (ref "C2") (pin "1") (pinfunction "1_1") (pintype "passive"))
      (node (ref "R3") (pin "1") (pinfunction "1_1") (pintype "passive"))
      (node (ref "U1") (pin "6") (pinfunction "PD1/OSC_OUT_6") (pintype "passive"))
      (node (ref "Y1") (pin "1") (pinfunction "OSC1_1") (pintype "passive"))
    )
    (net (code "43") (name "Net-(U1-PDO{slash}OSC_IN)") (class "Default")
      (node (ref "C1") (pin "1") (pinfunction "1_1") (pintype "passive"))
      (node (ref "R3") (pin "2") (pinfunction "2_2") (pintype "passive"))
      (node (ref "U1") (pin "5") (pinfunction "PDO/OSC_IN_5") (pintype "passive"))
      (node (ref "Y1") (pin "2") (pinfunction "OSC2_2") (pintype "passive"))
    )
    (net (code "44") (name "Net-(U2-VIN)") (class "Default")
      (node (ref "C6") (pin "1") (pinfunction "1_1") (pintype "passive"))
      (node (ref "C7") (pin "2") (pinfunction "2_2") (pintype "passive"))
      (node (ref "L1") (pin "1") (pinfunction "1_1") (pintype "passive"))
      (node (ref "U2") (pin "3") (pinfunction "VIN_3") (pintype "passive"))
    )
    (net (code "45") (name "VDD3V3") (class "Default")
      (node (ref "C10") (pin "2") (pinfunction "2_2") (pintype "passive"))
      (node (ref "C11") (pin "2") (pinfunction "2_2") (pintype "passive"))
      (node (ref "C12") (pin "1") (pinfunction "1_1") (pintype "passive"))
      (node (ref "C13") (pin "1") (pinfunction "1_1") (pintype "passive"))
      (node (ref "C14") (pin "2") (pinfunction "2_2") (pintype "passive"))
      (node (ref "C15") (pin "2") (pinfunction "2_2") (pintype "passive"))
      (node (ref "C16") (pin "2") (pinfunction "2_2") (pintype "passive"))
      (node (ref "C8") (pin "2") (pinfunction "2_2") (pintype "passive"))
      (node (ref "C9") (pin "2") (pinfunction "2_2") (pintype "passive"))
      (node (ref "JP1") (pin "1") (pinfunction "1_1") (pintype "passive"))
      (node (ref "JP1") (pin "2") (pinfunction "2_2") (pintype "passive"))
      (node (ref "LD1") (pin "1") (pinfunction "A_1") (pintype "passive"))
      (node (ref "LD2") (pin "1") (pinfunction "A_1") (pintype "passive"))
      (node (ref "LD3") (pin "1") (pinfunction "A_1") (pintype "passive"))
      (node (ref "Q1") (pin "2") (pinfunction "E_2") (pintype "input"))
      (node (ref "R1") (pin "2") (pinfunction "2_2") (pintype "passive"))
      (node (ref "R10") (pin "1") (pinfunction "1_1") (pintype "passive"))
      (node (ref "R11") (pin "2") (pinfunction "2_2") (pintype "passive"))
      (node (ref "R12") (pin "2") (pinfunction "2_2") (pintype "passive"))
      (node (ref "R13") (pin "2") (pinfunction "2_2") (pintype "passive"))
      (node (ref "R17") (pin "2") (pinfunction "10_2") (pintype "passive"))
      (node (ref "R18") (pin "1") (pinfunction "1_1") (pintype "passive"))
      (node (ref "R19") (pin "1") (pinfunction "1_1") (pintype "passive"))
      (node (ref "R20") (pin "1") (pinfunction "1_1") (pintype "passive"))
      (node (ref "R21") (pin "1") (pinfunction "1_1") (pintype "passive"))
      (node (ref "R22") (pin "1") (pinfunction "1_1") (pintype "passive"))
      (node (ref "R23") (pin "1") (pinfunction "1_1") (pintype "passive"))
      (node (ref "R25") (pin "1") (pinfunction "1_1") (pintype "passive"))
      (node (ref "R26") (pin "1") (pinfunction "1_1") (pintype "passive"))
      (node (ref "R27") (pin "1") (pinfunction "1_1") (pintype "passive"))
      (node (ref "R28") (pin "1") (pinfunction "1_1") (pintype "passive"))
      (node (ref "R29") (pin "1") (pinfunction "1_1") (pintype "passive"))
      (node (ref "R30") (pin "1") (pinfunction "1_1") (pintype "passive"))
      (node (ref "R9") (pin "2") (pinfunction "2_2") (pintype "passive"))
      (node (ref "U1") (pin "1") (pinfunction "VBAT_1") (pintype "passive"))
      (node (ref "U1") (pin "24") (pinfunction "VDD_1_24") (pintype "passive"))
      (node (ref "U1") (pin "36") (pinfunction "VDD_2_36") (pintype "passive"))
      (node (ref "U1") (pin "48") (pinfunction "VDD_3_48") (pintype "passive"))
      (node (ref "U1") (pin "9") (pinfunction "VDDA_9") (pintype "passive"))
      (node (ref "U2") (pin "2") (pinfunction "OUT_2") (pintype "passive"))
      (node (ref "U2") (pin "4") (pinfunction "OUT_4") (pintype "passive"))
    )
    (net (code "46") (name "VIN-5V0") (class "Default")
      (node (ref "C5") (pin "1") (pinfunction "1_1") (pintype "passive"))
      (node (ref "L1") (pin "2") (pinfunction "2_2") (pintype "passive"))
      (node (ref "P2") (pin "1") (pinfunction "1_1") (pintype "passive"))
    )
    (net (code "47") (name "unconnected-(JP1-Pad4)") (class "Default")
      (node (ref "JP1") (pin "4") (pinfunction "4_4") (pintype "passive"))
    )
    (net (code "48") (name "unconnected-(U1-PB1{slash}ADC_IN9{slash}TIM3_CH4-Pad19)") (class "Default")
      (node (ref "U1") (pin "19") (pinfunction "PB1/ADC_IN9/TIM3_CH4_19") (pintype "passive"))
    )
    (net (code "49") (name "unconnected-(U1-PB5{slash}I2C1_SMBA1-Pad41)") (class "Default")
      (node (ref "U1") (pin "41") (pinfunction "PB5/I2C1_SMBA1_41") (pintype "passive"))
    )
    (net (code "50") (name "unconnected-(U1-PB8{slash}TIM4_CH3-Pad45)") (class "Default")
      (node (ref "U1") (pin "45") (pinfunction "PB8/TIM4_CH3_45") (pintype "passive"))
    )
    (net (code "51") (name "unconnected-(U1-PB10{slash}I2C2_SCL{slash}USART3_TX-Pad21)") (class "Default")
      (node (ref "U1") (pin "21") (pinfunction "PB10/I2C2_SCL/USART3_TX_21") (pintype "passive"))
    )
    (net (code "52") (name "unconnected-(U1-PB11{slash}I2C2_SDA{slash}USART3_RX-Pad22)") (class "Default")
      (node (ref "U1") (pin "22") (pinfunction "PB11/I2C2_SDA/USART3_RX_22") (pintype "passive"))
    )
    (net (code "53") (name "unconnected-(U1-PB12{slash}SPI2_NSS{slash}I2C2_SMBA1{slash}USART3_CK{slash}TIM1_BKIN-Pad25)") (class "Default")
      (node (ref "U1") (pin "25") (pinfunction "PB12/SPI2_NSS/I2C2_SMBA1/USART3_CK/TIM1_BKIN_25") (pintype "passive"))
    )
    (net (code "54") (name "unconnected-(U1-PC14{slash}OSC32_IN-Pad3)") (class "Default")
      (node (ref "U1") (pin "3") (pinfunction "PC14/OSC32_IN_3") (pintype "passive"))
    )
    (net (code "55") (name "unconnected-(U1-PC15{slash}OSC32_OUT-Pad4)") (class "Default")
      (node (ref "U1") (pin "4") (pinfunction "PC15/OSC32_OUT_4") (pintype "passive"))
    )
  )
)
